# M452xx.net
KiCad netlist of a schematic drawn in EAGLE
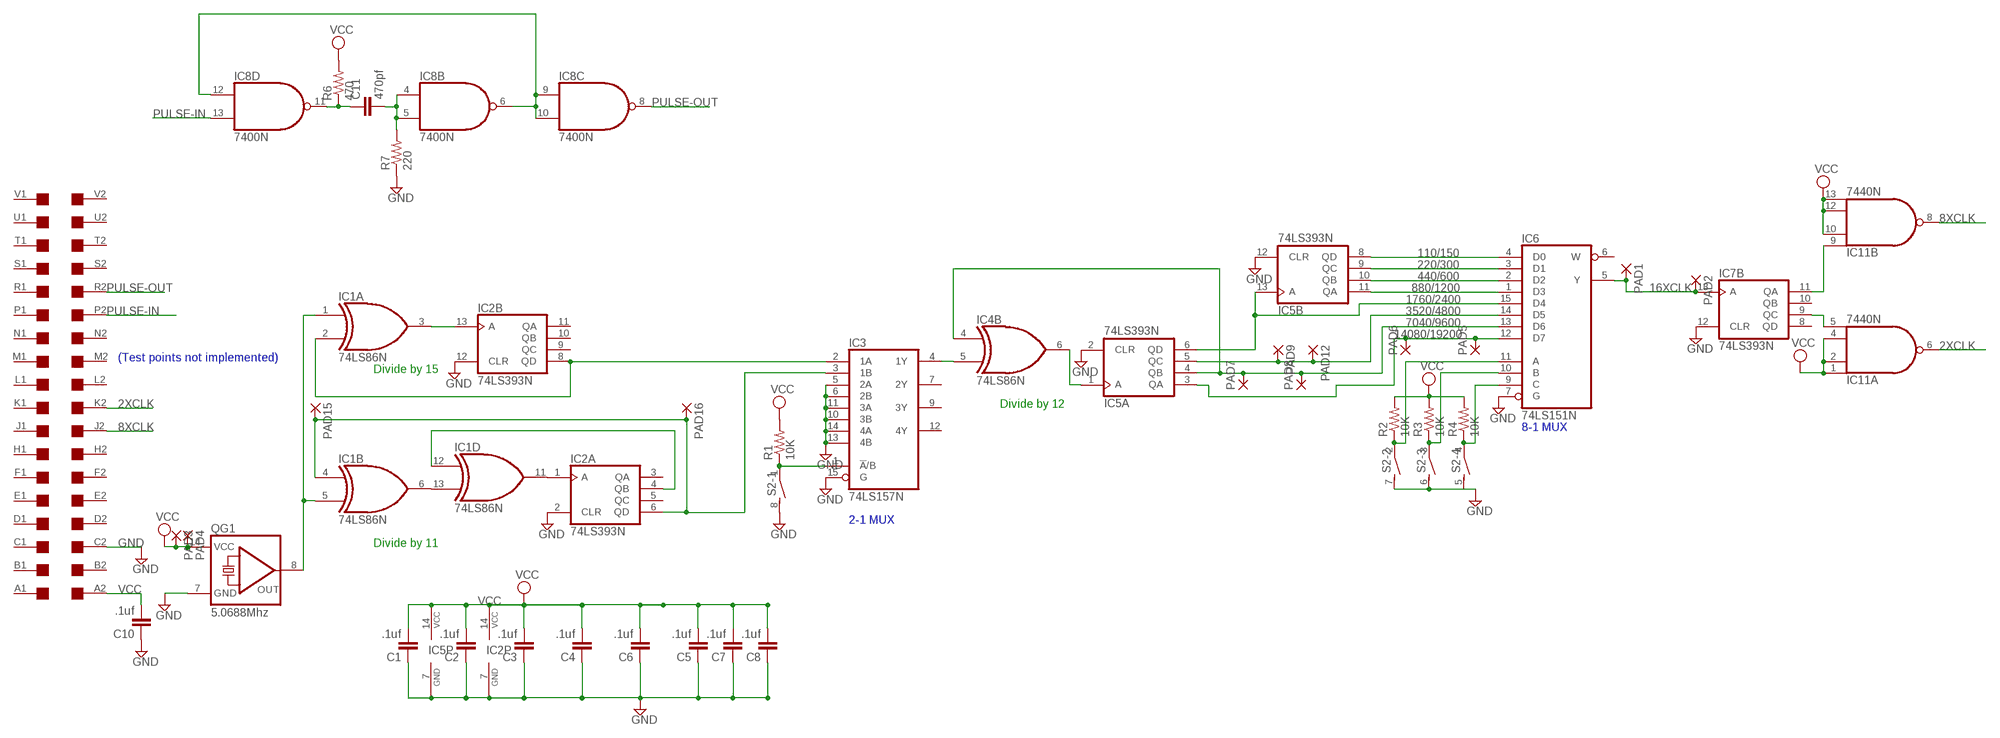
[diagram p0: schematic, sheet 1]

(export (version "E")
  (design (tool "Eeschema 10.0.6"))
  (components
    (comp (ref "C1")
      (value ".1uf")
      (footprint "eagle-import:C050-025X075")
      (libsource (lib "eagle-import") (part "C-EU050-025X075"))
    )
    (comp (ref "C2")
      (value ".1uf")
      (footprint "eagle-import:C050-025X075")
      (libsource (lib "eagle-import") (part "C-EU050-025X075"))
    )
    (comp (ref "C3")
      (value ".1uf")
      (footprint "eagle-import:C050-025X075")
      (libsource (lib "eagle-import") (part "C-EU050-025X075"))
    )
    (comp (ref "C4")
      (value ".1uf")
      (footprint "eagle-import:C050-025X075")
      (libsource (lib "eagle-import") (part "C-EU050-025X075"))
    )
    (comp (ref "C5")
      (value ".1uf")
      (footprint "eagle-import:C050-025X075")
      (libsource (lib "eagle-import") (part "C-EU050-025X075"))
    )
    (comp (ref "C6")
      (value ".1uf")
      (footprint "eagle-import:C050-025X075")
      (libsource (lib "eagle-import") (part "C-EU050-025X075"))
    )
    (comp (ref "C7")
      (value ".1uf")
      (footprint "eagle-import:C050-025X075")
      (libsource (lib "eagle-import") (part "C-EU050-025X075"))
    )
    (comp (ref "C8")
      (value ".1uf")
      (footprint "eagle-import:C050-025X075")
      (libsource (lib "eagle-import") (part "C-EU050-025X075"))
    )
    (comp (ref "C10")
      (value ".1uf")
      (footprint "eagle-import:C050-025X075")
      (libsource (lib "eagle-import") (part "C-EU050-025X075"))
    )
    (comp (ref "C11")
      (value "470pf")
      (footprint "eagle-import:C050-025X075")
      (libsource (lib "eagle-import") (part "C-EU050-025X075"))
    )
    (comp (ref "IC1")
      (value "74LS86N")
      (footprint "eagle-import:DIL14")
      (libsource (lib "eagle-import") (part "7486NLS"))
    )
    (comp (ref "IC2")
      (value "74LS393N")
      (footprint "eagle-import:DIL14")
      (libsource (lib "eagle-import") (part "74393NLS"))
    )
    (comp (ref "IC3")
      (value "74LS157N")
      (footprint "eagle-import:DIL16")
      (libsource (lib "eagle-import") (part "74157NLS"))
    )
    (comp (ref "IC4")
      (value "74LS86N")
      (footprint "eagle-import:DIL14")
      (libsource (lib "eagle-import") (part "7486NLS"))
    )
    (comp (ref "IC5")
      (value "74LS393N")
      (footprint "eagle-import:DIL14")
      (libsource (lib "eagle-import") (part "74393NLS"))
    )
    (comp (ref "IC6")
      (value "74LS151N")
      (footprint "eagle-import:DIL16")
      (libsource (lib "eagle-import") (part "74151N"))
    )
    (comp (ref "IC7")
      (value "74LS393N")
      (footprint "eagle-import:DIL14")
      (libsource (lib "eagle-import") (part "74393NLS"))
    )
    (comp (ref "IC8")
      (value "7400N")
      (footprint "eagle-import:DIL14")
      (libsource (lib "eagle-import") (part "7400N"))
    )
    (comp (ref "IC11")
      (value "7440N")
      (footprint "eagle-import:DIL14")
      (libsource (lib "eagle-import") (part "7420NS"))
    )
    (comp (ref "PAD1")
      (value "1,6/0,8")
      (footprint "eagle-import:1,6_0,8")
      (libsource (lib "eagle-import") (part "1,6/0,8"))
    )
    (comp (ref "PAD2")
      (value "1,6/0,8")
      (footprint "eagle-import:1,6_0,8")
      (libsource (lib "eagle-import") (part "1,6/0,8"))
    )
    (comp (ref "PAD3")
      (value "1,6/0,8")
      (footprint "eagle-import:1,6_0,8")
      (libsource (lib "eagle-import") (part "1,6/0,8"))
    )
    (comp (ref "PAD4")
      (value "1,6/0,8")
      (footprint "eagle-import:1,6_0,8")
      (libsource (lib "eagle-import") (part "1,6/0,8"))
    )
    (comp (ref "PAD5")
      (value "1,6/0,8")
      (footprint "eagle-import:1,6_0,8")
      (libsource (lib "eagle-import") (part "1,6/0,8"))
    )
    (comp (ref "PAD6")
      (value "1,6/0,8")
      (footprint "eagle-import:1,6_0,8")
      (libsource (lib "eagle-import") (part "1,6/0,8"))
    )
    (comp (ref "PAD7")
      (value "1,6/0,8")
      (footprint "eagle-import:1,6_0,8")
      (libsource (lib "eagle-import") (part "1,6/0,8"))
    )
    (comp (ref "PAD8")
      (value "1,6/0,8")
      (footprint "eagle-import:1,6_0,8")
      (libsource (lib "eagle-import") (part "1,6/0,8"))
    )
    (comp (ref "PAD9")
      (value "1,6/0,8")
      (footprint "eagle-import:1,6_0,8")
      (libsource (lib "eagle-import") (part "1,6/0,8"))
    )
    (comp (ref "PAD12")
      (value "1,6/0,8")
      (footprint "eagle-import:1,6_0,8")
      (libsource (lib "eagle-import") (part "1,6/0,8"))
    )
    (comp (ref "PAD15")
      (value "1,6/0,8")
      (footprint "eagle-import:1,6_0,8")
      (libsource (lib "eagle-import") (part "1,6/0,8"))
    )
    (comp (ref "PAD16")
      (value "1,6/0,8")
      (footprint "eagle-import:1,6_0,8")
      (libsource (lib "eagle-import") (part "1,6/0,8"))
    )
    (comp (ref "QG1")
      (value "5.0688Mhz")
      (footprint "eagle-import:DIL14S")
      (libsource (lib "eagle-import") (part "QG5860"))
    )
    (comp (ref "R1")
      (value "10K")
      (footprint "eagle-import:0204_7")
      (libsource (lib "eagle-import") (part "R-US_0204/7"))
    )
    (comp (ref "R2")
      (value "10K")
      (footprint "eagle-import:0204_7")
      (libsource (lib "eagle-import") (part "R-US_0204/7"))
    )
    (comp (ref "R3")
      (value "10K")
      (footprint "eagle-import:0204_7")
      (libsource (lib "eagle-import") (part "R-US_0204/7"))
    )
    (comp (ref "R4")
      (value "10K")
      (footprint "eagle-import:0204_7")
      (libsource (lib "eagle-import") (part "R-US_0204/7"))
    )
    (comp (ref "R6")
      (value "470")
      (footprint "eagle-import:0204_7")
      (libsource (lib "eagle-import") (part "R-US_0204/7"))
    )
    (comp (ref "R7")
      (value "220")
      (footprint "eagle-import:0204_7")
      (libsource (lib "eagle-import") (part "R-US_0204/7"))
    )
    (comp (ref "S2")
      (value "DIP04S")
      (footprint "eagle-import:DIP04S")
      (libsource (lib "eagle-import") (part "DIP04S"))
    )
    (comp (ref "U$1")
      (value "DEC-FLIPCHIP")
      (footprint "eagle-import:DEC-FLIPCHIP")
      (libsource (lib "eagle-import") (part "DEC-FLIPCHIP"))
    )
  )
  (nets
    (net (code "1") (name "/2XCLK") (class "Default")
      (node (ref "IC11") (pin "6") (pinfunction "O_6") (pintype "output"))
      (node (ref "U$1") (pin "K2") (pinfunction "K2_K2") (pintype "passive"))
    )
    (net (code "2") (name "/8XCLK") (class "Default")
      (node (ref "IC11") (pin "8") (pinfunction "O_8") (pintype "output"))
      (node (ref "U$1") (pin "J2") (pinfunction "J2_J2") (pintype "passive"))
    )
    (net (code "3") (name "/16XCLK") (class "Default")
      (node (ref "IC6") (pin "5") (pinfunction "Y_5") (pintype "output"))
      (node (ref "IC7") (pin "13") (pinfunction "A_13") (pintype "input"))
      (node (ref "PAD1") (pin "1") (pinfunction "P_1") (pintype "passive"))
      (node (ref "PAD2") (pin "1") (pinfunction "P_1") (pintype "passive"))
    )
    (net (code "4") (name "/110{slash}150") (class "Default")
      (node (ref "IC5") (pin "8") (pinfunction "QD_8") (pintype "output"))
      (node (ref "IC6") (pin "4") (pinfunction "D0_4") (pintype "input"))
    )
    (net (code "5") (name "/220{slash}300") (class "Default")
      (node (ref "IC5") (pin "9") (pinfunction "QC_9") (pintype "output"))
      (node (ref "IC6") (pin "3") (pinfunction "D1_3") (pintype "input"))
    )
    (net (code "6") (name "/440{slash}600") (class "Default")
      (node (ref "IC5") (pin "10") (pinfunction "QB_10") (pintype "output"))
      (node (ref "IC6") (pin "2") (pinfunction "D2_2") (pintype "input"))
    )
    (net (code "7") (name "/880{slash}1200") (class "Default")
      (node (ref "IC5") (pin "11") (pinfunction "QA_11") (pintype "output"))
      (node (ref "IC6") (pin "1") (pinfunction "D3_1") (pintype "input"))
    )
    (net (code "8") (name "/1760{slash}2400") (class "Default")
      (node (ref "IC5") (pin "13") (pinfunction "A_13") (pintype "input"))
      (node (ref "IC5") (pin "6") (pinfunction "QD_6") (pintype "output"))
      (node (ref "IC6") (pin "15") (pinfunction "D4_15") (pintype "input"))
    )
    (net (code "9") (name "/3520{slash}4800") (class "Default")
      (node (ref "IC5") (pin "5") (pinfunction "QC_5") (pintype "output"))
      (node (ref "IC6") (pin "14") (pinfunction "D5_14") (pintype "input"))
      (node (ref "PAD12") (pin "1") (pinfunction "P_1") (pintype "passive"))
      (node (ref "PAD9") (pin "1") (pinfunction "P_1") (pintype "passive"))
    )
    (net (code "10") (name "/7040{slash}9600") (class "Default")
      (node (ref "IC4") (pin "4") (pinfunction "I0_4") (pintype "input"))
      (node (ref "IC5") (pin "4") (pinfunction "QB_4") (pintype "output"))
      (node (ref "IC6") (pin "13") (pinfunction "D6_13") (pintype "input"))
      (node (ref "PAD7") (pin "1") (pinfunction "P_1") (pintype "passive"))
      (node (ref "PAD8") (pin "1") (pinfunction "P_1") (pintype "passive"))
    )
    (net (code "11") (name "/14080{slash}19200") (class "Default")
      (node (ref "IC5") (pin "3") (pinfunction "QA_3") (pintype "output"))
      (node (ref "IC6") (pin "12") (pinfunction "D7_12") (pintype "input"))
      (node (ref "PAD5") (pin "1") (pinfunction "P_1") (pintype "passive"))
      (node (ref "PAD6") (pin "1") (pinfunction "P_1") (pintype "passive"))
    )
    (net (code "12") (name "/PULSE-IN") (class "Default")
      (node (ref "IC8") (pin "13") (pinfunction "I1_13") (pintype "input"))
      (node (ref "U$1") (pin "P2") (pinfunction "P2_P2") (pintype "passive"))
    )
    (net (code "13") (name "/PULSE-OUT") (class "Default")
      (node (ref "IC8") (pin "8") (pinfunction "O_8") (pintype "output"))
      (node (ref "U$1") (pin "R2") (pinfunction "R2_R2") (pintype "passive"))
    )
    (net (code "14") (name "GND") (class "Default")
      (node (ref "C1") (pin "1") (pinfunction "1_1") (pintype "passive"))
      (node (ref "C10") (pin "1") (pinfunction "1_1") (pintype "passive"))
      (node (ref "C2") (pin "1") (pinfunction "1_1") (pintype "passive"))
      (node (ref "C3") (pin "1") (pinfunction "1_1") (pintype "passive"))
      (node (ref "C4") (pin "1") (pinfunction "1_1") (pintype "passive"))
      (node (ref "C5") (pin "1") (pinfunction "1_1") (pintype "passive"))
      (node (ref "C6") (pin "1") (pinfunction "1_1") (pintype "passive"))
      (node (ref "C7") (pin "1") (pinfunction "1_1") (pintype "passive"))
      (node (ref "C8") (pin "1") (pinfunction "1_1") (pintype "passive"))
      (node (ref "IC2") (pin "12") (pinfunction "CLR_12") (pintype "input"))
      (node (ref "IC2") (pin "2") (pinfunction "CLR_2") (pintype "input"))
      (node (ref "IC2") (pin "7") (pinfunction "GND_7") (pintype "power_in"))
      (node (ref "IC3") (pin "10") (pinfunction "3B_10") (pintype "input"))
      (node (ref "IC3") (pin "11") (pinfunction "3A_11") (pintype "input"))
      (node (ref "IC3") (pin "13") (pinfunction "4B_13") (pintype "input"))
      (node (ref "IC3") (pin "14") (pinfunction "4A_14") (pintype "input"))
      (node (ref "IC3") (pin "15") (pinfunction "G_15") (pintype "input"))
      (node (ref "IC3") (pin "5") (pinfunction "2A_5") (pintype "input"))
      (node (ref "IC3") (pin "6") (pinfunction "2B_6") (pintype "input"))
      (node (ref "IC5") (pin "12") (pinfunction "CLR_12") (pintype "input"))
      (node (ref "IC5") (pin "2") (pinfunction "CLR_2") (pintype "input"))
      (node (ref "IC5") (pin "7") (pinfunction "GND_7") (pintype "power_in"))
      (node (ref "IC6") (pin "7") (pinfunction "G_7") (pintype "input"))
      (node (ref "IC7") (pin "12") (pinfunction "CLR_12") (pintype "input"))
      (node (ref "QG1") (pin "7") (pinfunction "GND_7") (pintype "power_in"))
      (node (ref "R7") (pin "1") (pinfunction "1_1") (pintype "passive"))
      (node (ref "S2") (pin "5") (pinfunction "2_5") (pintype "passive"))
      (node (ref "S2") (pin "6") (pinfunction "2_6") (pintype "passive"))
      (node (ref "S2") (pin "7") (pinfunction "2_7") (pintype "passive"))
      (node (ref "S2") (pin "8") (pinfunction "2_8") (pintype "passive"))
      (node (ref "U$1") (pin "C2") (pinfunction "C2_C2") (pintype "passive"))
    )
    (net (code "15") (name "Net-(IC1A-I0)") (class "Default")
      (node (ref "IC1") (pin "1") (pinfunction "I0_1") (pintype "input"))
      (node (ref "IC1") (pin "5") (pinfunction "I1_5") (pintype "input"))
      (node (ref "QG1") (pin "8") (pinfunction "OUT_8") (pintype "output"))
    )
    (net (code "16") (name "Net-(IC1A-I1)") (class "Default")
      (node (ref "IC1") (pin "2") (pinfunction "I1_2") (pintype "input"))
      (node (ref "IC2") (pin "8") (pinfunction "QD_8") (pintype "output"))
      (node (ref "IC3") (pin "2") (pinfunction "1A_2") (pintype "input"))
    )
    (net (code "17") (name "Net-(IC1A-O)") (class "Default")
      (node (ref "IC1") (pin "3") (pinfunction "O_3") (pintype "output"))
      (node (ref "IC2") (pin "13") (pinfunction "A_13") (pintype "input"))
    )
    (net (code "18") (name "Net-(IC1B-I0)") (class "Default")
      (node (ref "IC1") (pin "4") (pinfunction "I0_4") (pintype "input"))
      (node (ref "IC2") (pin "6") (pinfunction "QD_6") (pintype "output"))
      (node (ref "IC3") (pin "3") (pinfunction "1B_3") (pintype "input"))
      (node (ref "PAD15") (pin "1") (pinfunction "P_1") (pintype "passive"))
      (node (ref "PAD16") (pin "1") (pinfunction "P_1") (pintype "passive"))
    )
    (net (code "19") (name "Net-(IC1B-O)") (class "Default")
      (node (ref "IC1") (pin "13") (pinfunction "I1_13") (pintype "input"))
      (node (ref "IC1") (pin "6") (pinfunction "O_6") (pintype "output"))
    )
    (net (code "20") (name "Net-(IC1D-I0)") (class "Default")
      (node (ref "IC1") (pin "12") (pinfunction "I0_12") (pintype "input"))
      (node (ref "IC2") (pin "4") (pinfunction "QB_4") (pintype "output"))
    )
    (net (code "21") (name "Net-(IC1D-O)") (class "Default")
      (node (ref "IC1") (pin "11") (pinfunction "O_11") (pintype "output"))
      (node (ref "IC2") (pin "1") (pinfunction "A_1") (pintype "input"))
    )
    (net (code "22") (name "Net-(IC3A-1Y)") (class "Default")
      (node (ref "IC3") (pin "4") (pinfunction "1Y_4") (pintype "output"))
      (node (ref "IC4") (pin "5") (pinfunction "I1_5") (pintype "input"))
    )
    (net (code "23") (name "Net-(IC3A-~{A}{slash}B)") (class "Default")
      (node (ref "IC3") (pin "1") (pinfunction "~{A}/B_1") (pintype "input"))
      (node (ref "R1") (pin "1") (pinfunction "1_1") (pintype "passive"))
      (node (ref "S2") (pin "1") (pinfunction "1_1") (pintype "passive"))
    )
    (net (code "24") (name "Net-(IC4B-O)") (class "Default")
      (node (ref "IC4") (pin "6") (pinfunction "O_6") (pintype "output"))
      (node (ref "IC5") (pin "1") (pinfunction "A_1") (pintype "input"))
    )
    (net (code "25") (name "Net-(IC6A-A)") (class "Default")
      (node (ref "IC6") (pin "11") (pinfunction "A_11") (pintype "input"))
      (node (ref "R2") (pin "1") (pinfunction "1_1") (pintype "passive"))
      (node (ref "S2") (pin "2") (pinfunction "1_2") (pintype "passive"))
    )
    (net (code "26") (name "Net-(IC6A-B)") (class "Default")
      (node (ref "IC6") (pin "10") (pinfunction "B_10") (pintype "input"))
      (node (ref "R3") (pin "1") (pinfunction "1_1") (pintype "passive"))
      (node (ref "S2") (pin "3") (pinfunction "1_3") (pintype "passive"))
    )
    (net (code "27") (name "Net-(IC6A-C)") (class "Default")
      (node (ref "IC6") (pin "9") (pinfunction "C_9") (pintype "input"))
      (node (ref "R4") (pin "1") (pinfunction "1_1") (pintype "passive"))
      (node (ref "S2") (pin "4") (pinfunction "1_4") (pintype "passive"))
    )
    (net (code "28") (name "Net-(IC8B-I0)") (class "Default")
      (node (ref "C11") (pin "2") (pinfunction "2_2") (pintype "passive"))
      (node (ref "IC8") (pin "4") (pinfunction "I0_4") (pintype "input"))
      (node (ref "IC8") (pin "5") (pinfunction "I1_5") (pintype "input"))
      (node (ref "R7") (pin "2") (pinfunction "2_2") (pintype "passive"))
    )
    (net (code "29") (name "Net-(IC8B-O)") (class "Default")
      (node (ref "IC8") (pin "10") (pinfunction "I1_10") (pintype "input"))
      (node (ref "IC8") (pin "12") (pinfunction "I0_12") (pintype "input"))
      (node (ref "IC8") (pin "6") (pinfunction "O_6") (pintype "output"))
      (node (ref "IC8") (pin "9") (pinfunction "I0_9") (pintype "input"))
    )
    (net (code "30") (name "Net-(IC8D-O)") (class "Default")
      (node (ref "C11") (pin "1") (pinfunction "1_1") (pintype "passive"))
      (node (ref "IC8") (pin "11") (pinfunction "O_11") (pintype "output"))
      (node (ref "R6") (pin "1") (pinfunction "1_1") (pintype "passive"))
    )
    (net (code "31") (name "Net-(IC11A-I3)") (class "Default")
      (node (ref "IC11") (pin "5") (pinfunction "I3_5") (pintype "input"))
      (node (ref "IC7") (pin "9") (pinfunction "QC_9") (pintype "output"))
    )
    (net (code "32") (name "Net-(IC11B-I0)") (class "Default")
      (node (ref "IC11") (pin "9") (pinfunction "I0_9") (pintype "input"))
      (node (ref "IC7") (pin "11") (pinfunction "QA_11") (pintype "output"))
    )
    (net (code "33") (name "VCC") (class "Default")
      (node (ref "C1") (pin "2") (pinfunction "2_2") (pintype "passive"))
      (node (ref "C10") (pin "2") (pinfunction "2_2") (pintype "passive"))
      (node (ref "C2") (pin "2") (pinfunction "2_2") (pintype "passive"))
      (node (ref "C3") (pin "2") (pinfunction "2_2") (pintype "passive"))
      (node (ref "C4") (pin "2") (pinfunction "2_2") (pintype "passive"))
      (node (ref "C5") (pin "2") (pinfunction "2_2") (pintype "passive"))
      (node (ref "C6") (pin "2") (pinfunction "2_2") (pintype "passive"))
      (node (ref "C7") (pin "2") (pinfunction "2_2") (pintype "passive"))
      (node (ref "C8") (pin "2") (pinfunction "2_2") (pintype "passive"))
      (node (ref "IC11") (pin "1") (pinfunction "I0_1") (pintype "input"))
      (node (ref "IC11") (pin "10") (pinfunction "I1_10") (pintype "input"))
      (node (ref "IC11") (pin "12") (pinfunction "I2_12") (pintype "input"))
      (node (ref "IC11") (pin "13") (pinfunction "I3_13") (pintype "input"))
      (node (ref "IC11") (pin "2") (pinfunction "I1_2") (pintype "input"))
      (node (ref "IC11") (pin "4") (pinfunction "I2_4") (pintype "input"))
      (node (ref "IC2") (pin "14") (pinfunction "VCC_14") (pintype "power_in"))
      (node (ref "IC5") (pin "14") (pinfunction "VCC_14") (pintype "power_in"))
      (node (ref "PAD3") (pin "1") (pinfunction "P_1") (pintype "passive"))
      (node (ref "PAD4") (pin "1") (pinfunction "P_1") (pintype "passive"))
      (node (ref "QG1") (pin "14") (pinfunction "VCC_14") (pintype "power_in"))
      (node (ref "R1") (pin "2") (pinfunction "2_2") (pintype "passive"))
      (node (ref "R2") (pin "2") (pinfunction "2_2") (pintype "passive"))
      (node (ref "R3") (pin "2") (pinfunction "2_2") (pintype "passive"))
      (node (ref "R4") (pin "2") (pinfunction "2_2") (pintype "passive"))
      (node (ref "R6") (pin "2") (pinfunction "2_2") (pintype "passive"))
      (node (ref "U$1") (pin "A2") (pinfunction "A2_A2") (pintype "passive"))
    )
    (net (code "34") (name "unconnected-(IC2A-QA-Pad3)") (class "Default")
      (node (ref "IC2") (pin "3") (pinfunction "QA_3") (pintype "output"))
    )
    (net (code "35") (name "unconnected-(IC2A-QC-Pad5)") (class "Default")
      (node (ref "IC2") (pin "5") (pinfunction "QC_5") (pintype "output"))
    )
    (net (code "36") (name "unconnected-(IC2B-QA-Pad11)") (class "Default")
      (node (ref "IC2") (pin "11") (pinfunction "QA_11") (pintype "output"))
    )
    (net (code "37") (name "unconnected-(IC2B-QB-Pad10)") (class "Default")
      (node (ref "IC2") (pin "10") (pinfunction "QB_10") (pintype "output"))
    )
    (net (code "38") (name "unconnected-(IC2B-QC-Pad9)") (class "Default")
      (node (ref "IC2") (pin "9") (pinfunction "QC_9") (pintype "output"))
    )
    (net (code "39") (name "unconnected-(IC3A-2Y-Pad7)") (class "Default")
      (node (ref "IC3") (pin "7") (pinfunction "2Y_7") (pintype "output"))
    )
    (net (code "40") (name "unconnected-(IC3A-3Y-Pad9)") (class "Default")
      (node (ref "IC3") (pin "9") (pinfunction "3Y_9") (pintype "output"))
    )
    (net (code "41") (name "unconnected-(IC3A-4Y-Pad12)") (class "Default")
      (node (ref "IC3") (pin "12") (pinfunction "4Y_12") (pintype "output"))
    )
    (net (code "42") (name "unconnected-(IC6A-W-Pad6)") (class "Default")
      (node (ref "IC6") (pin "6") (pinfunction "W_6") (pintype "output"))
    )
    (net (code "43") (name "unconnected-(IC7B-QB-Pad10)") (class "Default")
      (node (ref "IC7") (pin "10") (pinfunction "QB_10") (pintype "output"))
    )
    (net (code "44") (name "unconnected-(IC7B-QD-Pad8)") (class "Default")
      (node (ref "IC7") (pin "8") (pinfunction "QD_8") (pintype "output"))
    )
    (net (code "45") (name "unconnected-(U$1-PadA1)") (class "Default")
      (node (ref "U$1") (pin "A1") (pinfunction "A1_A1") (pintype "passive"))
    )
    (net (code "46") (name "unconnected-(U$1-PadB1)") (class "Default")
      (node (ref "U$1") (pin "B1") (pinfunction "B1_B1") (pintype "passive"))
    )
    (net (code "47") (name "unconnected-(U$1-PadB2)") (class "Default")
      (node (ref "U$1") (pin "B2") (pinfunction "B2_B2") (pintype "passive"))
    )
    (net (code "48") (name "unconnected-(U$1-PadC1)") (class "Default")
      (node (ref "U$1") (pin "C1") (pinfunction "C1_C1") (pintype "passive"))
    )
    (net (code "49") (name "unconnected-(U$1-PadD1)") (class "Default")
      (node (ref "U$1") (pin "D1") (pinfunction "D1_D1") (pintype "passive"))
    )
    (net (code "50") (name "unconnected-(U$1-PadD2)") (class "Default")
      (node (ref "U$1") (pin "D2") (pinfunction "D2_D2") (pintype "passive"))
    )
    (net (code "51") (name "unconnected-(U$1-PadE1)") (class "Default")
      (node (ref "U$1") (pin "E1") (pinfunction "E1_E1") (pintype "passive"))
    )
    (net (code "52") (name "unconnected-(U$1-PadE2)") (class "Default")
      (node (ref "U$1") (pin "E2") (pinfunction "E2_E2") (pintype "passive"))
    )
    (net (code "53") (name "unconnected-(U$1-PadF1)") (class "Default")
      (node (ref "U$1") (pin "F1") (pinfunction "F1_F1") (pintype "passive"))
    )
    (net (code "54") (name "unconnected-(U$1-PadF2)") (class "Default")
      (node (ref "U$1") (pin "F2") (pinfunction "F2_F2") (pintype "passive"))
    )
    (net (code "55") (name "unconnected-(U$1-PadH1)") (class "Default")
      (node (ref "U$1") (pin "H1") (pinfunction "H1_H1") (pintype "passive"))
    )
    (net (code "56") (name "unconnected-(U$1-PadH2)") (class "Default")
      (node (ref "U$1") (pin "H2") (pinfunction "H2_H2") (pintype "passive"))
    )
    (net (code "57") (name "unconnected-(U$1-PadJ1)") (class "Default")
      (node (ref "U$1") (pin "J1") (pinfunction "J1_J1") (pintype "passive"))
    )
    (net (code "58") (name "unconnected-(U$1-PadK1)") (class "Default")
      (node (ref "U$1") (pin "K1") (pinfunction "K1_K1") (pintype "passive"))
    )
    (net (code "59") (name "unconnected-(U$1-PadL1)") (class "Default")
      (node (ref "U$1") (pin "L1") (pinfunction "L1_L1") (pintype "passive"))
    )
    (net (code "60") (name "unconnected-(U$1-PadL2)") (class "Default")
      (node (ref "U$1") (pin "L2") (pinfunction "L2_L2") (pintype "passive"))
    )
    (net (code "61") (name "unconnected-(U$1-PadM1)") (class "Default")
      (node (ref "U$1") (pin "M1") (pinfunction "M1_M1") (pintype "passive"))
    )
    (net (code "62") (name "unconnected-(U$1-PadM2)") (class "Default")
      (node (ref "U$1") (pin "M2") (pinfunction "M2_M2") (pintype "passive"))
    )
    (net (code "63") (name "unconnected-(U$1-PadN1)") (class "Default")
      (node (ref "U$1") (pin "N1") (pinfunction "N1_N1") (pintype "passive"))
    )
    (net (code "64") (name "unconnected-(U$1-PadN2)") (class "Default")
      (node (ref "U$1") (pin "N2") (pinfunction "N2_N2") (pintype "passive"))
    )
    (net (code "65") (name "unconnected-(U$1-PadP1)") (class "Default")
      (node (ref "U$1") (pin "P1") (pinfunction "P1_P1") (pintype "passive"))
    )
    (net (code "66") (name "unconnected-(U$1-PadR1)") (class "Default")
      (node (ref "U$1") (pin "R1") (pinfunction "R1_R1") (pintype "passive"))
    )
    (net (code "67") (name "unconnected-(U$1-PadS1)") (class "Default")
      (node (ref "U$1") (pin "S1") (pinfunction "S1_S1") (pintype "passive"))
    )
    (net (code "68") (name "unconnected-(U$1-PadS2)") (class "Default")
      (node (ref "U$1") (pin "S2") (pinfunction "S2_S2") (pintype "passive"))
    )
    (net (code "69") (name "unconnected-(U$1-PadT1)") (class "Default")
      (node (ref "U$1") (pin "T1") (pinfunction "T1_T1") (pintype "passive"))
    )
    (net (code "70") (name "unconnected-(U$1-PadT2)") (class "Default")
      (node (ref "U$1") (pin "T2") (pinfunction "T2_T2") (pintype "passive"))
    )
    (net (code "71") (name "unconnected-(U$1-PadU1)") (class "Default")
      (node (ref "U$1") (pin "U1") (pinfunction "U1_U1") (pintype "passive"))
    )
    (net (code "72") (name "unconnected-(U$1-PadU2)") (class "Default")
      (node (ref "U$1") (pin "U2") (pinfunction "U2_U2") (pintype "passive"))
    )
    (net (code "73") (name "unconnected-(U$1-PadV1)") (class "Default")
      (node (ref "U$1") (pin "V1") (pinfunction "V1_V1") (pintype "passive"))
    )
    (net (code "74") (name "unconnected-(U$1-PadV2)") (class "Default")
      (node (ref "U$1") (pin "V2") (pinfunction "V2_V2") (pintype "passive"))
    )
  )
)
